# 07_WiFi-BLE.net
KiCad netlist of a schematic drawn in Altium Designer
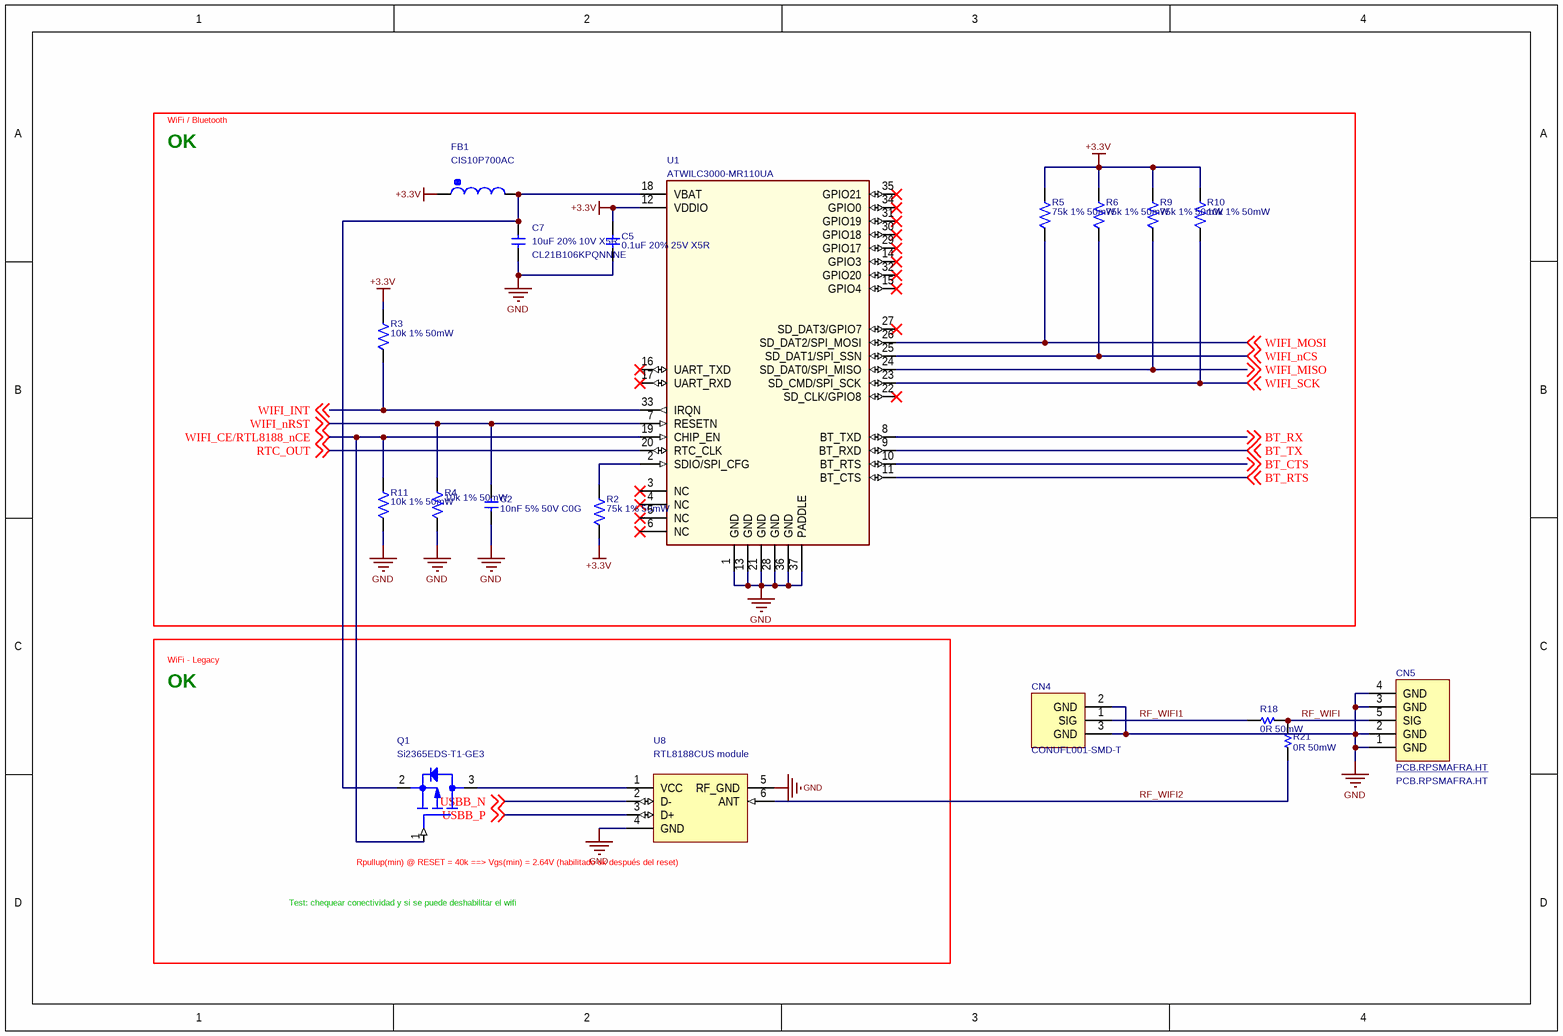
[diagram p0: 07_WiFi-BLE.SchDoc]

(export (version "E")
  (design (tool "Eeschema 10.0.6"))
  (components
    (comp (ref "C2")
      (value "10nF 5% 50V C0G")
      (footprint "CAPC1005N")
      (description "Capacitor, Ceramic")
      (fields
        (field (name "MFG") "<GENERIC>")
        (field (name "TOLERANCE") "5%")
        (field (name "FOOTPRINT CHECKED") "Assign OK, Footprint OK")
      )
      (libsource (lib "components") (part "C"))
    )
    (comp (ref "C5")
      (value "0.1uF 20% 25V X5R")
      (footprint "CAPC1005N")
      (description "Capacitor, Ceramic")
      (fields
        (field (name "MFG") "SAMSUNG")
        (field (name "TOLERANCE") "20%")
        (field (name "FOOTPRINT CHECKED") "Assign OK, Footprint OK")
      )
      (libsource (lib "*") (part "C_Dup1"))
    )
    (comp (ref "C7")
      (value "10uF 20% 10V X5R")
      (footprint "CAPC2012X140N")
      (description "Capacitor, Ceramic")
      (fields
        (field (name "MFG") "SAMSUNG")
        (field (name "MFG_PN") "CL21B106KPQNNNE")
        (field (name "TOLERANCE") "20%")
        (field (name "FOOTPRINT CHECKED") "Assign OK, Footprint OK")
      )
      (libsource (lib "*") (part "C_Dup1"))
    )
    (comp (ref "CN4")
      (value "CONUFL001-SMD-T")
      (footprint "U.FL-R-SMT-1")
      (description "Ultra Small Surface Mount Coaxial Connectors - 1.9mm or 2.4mm Mated Height")
      (fields (field (name "MFG") "LINX") (field (name "FOOTPRINT CHECKED") "Assign OK, Footprint OK"))
      (libsource (lib "traz") (part "U.FL-R-SMT-1"))
    )
    (comp (ref "CN5")
      (value "PCB.RPSMAFRA.HT")
      (footprint "0733910320")
      (description "RP-SMA, Right angle")
      (fields
        (field (name "MFG") "TAOGLAS")
        (field (name "MFG_PN") "PCB.RPSMAFRA.HT")
        (field (name "FOOTPRINT CHECKED") "Assign Ok, Footprint Ok")
      )
      (libsource (lib "xct") (part "RPSMA"))
    )
    (comp (ref "FB1")
      (value "CIS10P700AC")
      (footprint "INDC1608X95N")
      (description "Ferrite Bead")
      (fields (field (name "MFG") "SAMSUNG") (field (name "FOOTPRINT CHECKED") "Assign OK, Footprint OK"))
      (libsource (lib "*") (part "L"))
    )
    (comp (ref "Q1")
      (value "Si2365EDS-T1-GE3")
      (footprint "SOT95P230X110-3N")
      (description "MOSFET, P channel")
      (fields (field (name "MFG") "VISHAY") (field (name "FOOTPRINT CHECKED") "Assign OK, Footprint OK"))
      (libsource (lib "traz") (part "DMG1013UW"))
    )
    (comp (ref "R2")
      (value "75k 1% 50mW")
      (footprint "RESC1005X40N")
      (description "Resistor, SMD")
      (fields
        (field (name "MFG") "<GENERIC>")
        (field (name "POWER") "50mW")
        (field (name "FOOTPRINT CHECKED") "Assign OK, Footprint OK")
      )
      (libsource (lib "*") (part "R"))
    )
    (comp (ref "R3")
      (value "10k 1% 50mW")
      (footprint "RESC1005X40N")
      (description "Resistor, SMD")
      (fields
        (field (name "MFG") "<GENERIC>")
        (field (name "POWER") "50mW")
        (field (name "FOOTPRINT CHECKED") "Assign OK, Footprint OK")
      )
      (libsource (lib "*") (part "R"))
    )
    (comp (ref "R4")
      (value "10k 1% 50mW")
      (footprint "RESC1005X40N")
      (description "Resistor, SMD")
      (fields
        (field (name "MFG") "<GENERIC>")
        (field (name "POWER") "50mW")
        (field (name "FOOTPRINT CHECKED") "Assign OK, Footprint OK")
      )
      (libsource (lib "*") (part "R"))
    )
    (comp (ref "R5")
      (value "75k 1% 50mW")
      (footprint "RESC1005X40N")
      (description "Resistor, SMD")
      (fields
        (field (name "MFG") "<GENERIC>")
        (field (name "POWER") "50mW")
        (field (name "FOOTPRINT CHECKED") "Assign OK, Footprint OK")
      )
      (libsource (lib "*") (part "R"))
    )
    (comp (ref "R6")
      (value "75k 1% 50mW")
      (footprint "RESC1005X40N")
      (description "Resistor, SMD")
      (fields
        (field (name "MFG") "<GENERIC>")
        (field (name "POWER") "50mW")
        (field (name "FOOTPRINT CHECKED") "Assign OK, Footprint OK")
      )
      (libsource (lib "*") (part "R"))
    )
    (comp (ref "R9")
      (value "75k 1% 50mW")
      (footprint "RESC1005X40N")
      (description "Resistor, SMD")
      (fields
        (field (name "MFG") "<GENERIC>")
        (field (name "POWER") "50mW")
        (field (name "FOOTPRINT CHECKED") "Assign OK, Footprint OK")
      )
      (libsource (lib "*") (part "R"))
    )
    (comp (ref "R10")
      (value "10k 1% 50mW")
      (footprint "RESC1005X40N")
      (description "Resistor, SMD")
      (fields
        (field (name "MFG") "<GENERIC>")
        (field (name "POWER") "50mW")
        (field (name "FOOTPRINT CHECKED") "Assign OK, Footprint OK")
      )
      (libsource (lib "*") (part "R"))
    )
    (comp (ref "R11")
      (value "10k 1% 50mW")
      (footprint "RESC1005X40N")
      (description "Resistor, SMD")
      (fields
        (field (name "MFG") "<GENERIC>")
        (field (name "POWER") "50mW")
        (field (name "FOOTPRINT CHECKED") "Assign OK, Footprint OK")
      )
      (libsource (lib "*") (part "R"))
    )
    (comp (ref "R18")
      (value "0R 50mW")
      (footprint "RESC1005X40N")
      (description "Resistor, SMD")
      (fields
        (field (name "MFG") "<GENERIC>")
        (field (name "POWER") "50mW")
        (field (name "FOOTPRINT CHECKED") "Assign OK, Footprint OK")
      )
      (libsource (lib "components") (part "R"))
    )
    (comp (ref "R21")
      (value "0R 50mW")
      (footprint "RESC1005X40N")
      (description "Resistor, SMD")
      (fields
        (field (name "MFG") "<GENERIC>")
        (field (name "POWER") "50mW")
        (field (name "FOOTPRINT CHECKED") "Assign OK, Footprint OK")
      )
      (libsource (lib "components") (part "R"))
    )
    (comp (ref "U1")
      (value "ATWILC3000-MR110UA")
      (footprint "ATWILC3000-MR110CA")
      (description "IEEE 802.11 b/g/n Link Controller Module with Integrated Bluetooth 4.0")
      (fields (field (name "MFG") "MICROCHIP") (field (name "FOOTPRINT CHECKED") "Assign OK, Footprint OK"))
      (libsource (lib "MCHP-CDB") (part "MODULE ATWILC3000-MR110CA"))
    )
    (comp (ref "U8")
      (value "RTL8188CUS module")
      (footprint "GWF-7M01")
      (description "150Mbps IEEE 802.11 b/g/n WiFi Module")
      (fields (field (name "MFG") "FORMIKE") (field (name "FOOTPRINT CHECKED") "Assign OK, Footprint OK"))
      (libsource (lib "traz") (part "GWF-7M01"))
    )
  )
  (nets
    (net (code "1") (name "+3.3V") (class "Default")
      (node (ref "C5") (pin "2") (pinfunction "2_2") (pintype "passive"))
      (node (ref "FB1") (pin "1") (pinfunction "1_1") (pintype "passive"))
      (node (ref "R10") (pin "1") (pinfunction "1_1") (pintype "passive"))
      (node (ref "R2") (pin "2") (pinfunction "2_2") (pintype "passive"))
      (node (ref "R3") (pin "1") (pinfunction "1_1") (pintype "passive"))
      (node (ref "R5") (pin "1") (pinfunction "1_1") (pintype "passive"))
      (node (ref "R6") (pin "1") (pinfunction "1_1") (pintype "passive"))
      (node (ref "R9") (pin "1") (pinfunction "1_1") (pintype "passive"))
      (node (ref "U1") (pin "12") (pinfunction "VDDIO_12") (pintype "power_in"))
    )
    (net (code "2") (name "/RF_WIFI") (class "Default")
      (node (ref "CN5") (pin "5") (pinfunction "SIG_5") (pintype "passive"))
      (node (ref "R18") (pin "2") (pinfunction "2_2") (pintype "passive"))
      (node (ref "R21") (pin "2") (pinfunction "2_2") (pintype "passive"))
    )
    (net (code "3") (name "/RF_WIFI1") (class "Default")
      (node (ref "CN4") (pin "1") (pinfunction "SIG_1") (pintype "passive"))
      (node (ref "R18") (pin "1") (pinfunction "1_1") (pintype "passive"))
    )
    (net (code "4") (name "/RF_WIFI2") (class "Default")
      (node (ref "R21") (pin "1") (pinfunction "1_1") (pintype "passive"))
      (node (ref "U8") (pin "6") (pinfunction "ANT_6") (pintype "input"))
    )
    (net (code "5") (name "BT_CTS") (class "Default")
      (node (ref "U1") (pin "10") (pinfunction "BT_RTS_10") (pintype "bidirectional"))
    )
    (net (code "6") (name "BT_RTS") (class "Default")
      (node (ref "U1") (pin "11") (pinfunction "BT_CTS_11") (pintype "bidirectional"))
    )
    (net (code "7") (name "BT_RX") (class "Default")
      (node (ref "U1") (pin "8") (pinfunction "BT_TXD_8") (pintype "bidirectional"))
    )
    (net (code "8") (name "BT_TX") (class "Default")
      (node (ref "U1") (pin "9") (pinfunction "BT_RXD_9") (pintype "bidirectional"))
    )
    (net (code "9") (name "GND") (class "Default")
      (node (ref "C2") (pin "2") (pinfunction "2_2") (pintype "passive"))
      (node (ref "C5") (pin "1") (pinfunction "1_1") (pintype "passive"))
      (node (ref "C7") (pin "2") (pinfunction "2_2") (pintype "passive"))
      (node (ref "CN4") (pin "2") (pinfunction "GND_2") (pintype "passive"))
      (node (ref "CN4") (pin "3") (pinfunction "GND_3") (pintype "passive"))
      (node (ref "CN5") (pin "1") (pinfunction "GND_1") (pintype "passive"))
      (node (ref "CN5") (pin "2") (pinfunction "GND_2") (pintype "passive"))
      (node (ref "CN5") (pin "3") (pinfunction "GND_3") (pintype "passive"))
      (node (ref "CN5") (pin "4") (pinfunction "GND_4") (pintype "passive"))
      (node (ref "R11") (pin "2") (pinfunction "2_2") (pintype "passive"))
      (node (ref "R4") (pin "2") (pinfunction "2_2") (pintype "passive"))
      (node (ref "U1") (pin "1") (pinfunction "GND_1") (pintype "power_in"))
      (node (ref "U1") (pin "13") (pinfunction "GND_13") (pintype "power_in"))
      (node (ref "U1") (pin "21") (pinfunction "GND_21") (pintype "power_in"))
      (node (ref "U1") (pin "28") (pinfunction "GND_28") (pintype "power_in"))
      (node (ref "U1") (pin "36") (pinfunction "GND_36") (pintype "power_in"))
      (node (ref "U1") (pin "37") (pinfunction "PADDLE_37") (pintype "power_in"))
      (node (ref "U8") (pin "4") (pinfunction "GND_4") (pintype "power_in"))
      (node (ref "U8") (pin "5") (pinfunction "RF_GND_5") (pintype "power_in"))
    )
    (net (code "10") (name "Net-(Q1-DRAIN)") (class "Default")
      (node (ref "Q1") (pin "3") (pinfunction "DRAIN_3") (pintype "passive"))
      (node (ref "U8") (pin "1") (pinfunction "VCC_1") (pintype "power_in"))
    )
    (net (code "11") (name "Net-(Q1-SOURCE)") (class "Default")
      (node (ref "C7") (pin "1") (pinfunction "1_1") (pintype "passive"))
      (node (ref "FB1") (pin "2") (pinfunction "2_2") (pintype "passive"))
      (node (ref "Q1") (pin "2") (pinfunction "SOURCE_2") (pintype "passive"))
      (node (ref "U1") (pin "18") (pinfunction "VBAT_18") (pintype "power_in"))
    )
    (net (code "12") (name "Net-(U1-SDIO{slash}SPI_CFG)") (class "Default")
      (node (ref "R2") (pin "1") (pinfunction "1_1") (pintype "passive"))
      (node (ref "U1") (pin "2") (pinfunction "SDIO/SPI_CFG_2") (pintype "input"))
    )
    (net (code "13") (name "RTC_OUT") (class "Default")
      (node (ref "U1") (pin "20") (pinfunction "RTC_CLK_20") (pintype "bidirectional"))
    )
    (net (code "14") (name "USBB_N") (class "Default")
      (node (ref "U8") (pin "2") (pinfunction "D-_2") (pintype "bidirectional"))
    )
    (net (code "15") (name "USBB_P") (class "Default")
      (node (ref "U8") (pin "3") (pinfunction "D+_3") (pintype "bidirectional"))
    )
    (net (code "16") (name "WIFI_CE{slash}RTL8188_nCE") (class "Default")
      (node (ref "Q1") (pin "1") (pinfunction "GATE_1") (pintype "input"))
      (node (ref "R11") (pin "1") (pinfunction "1_1") (pintype "passive"))
      (node (ref "U1") (pin "19") (pinfunction "CHIP_EN_19") (pintype "input"))
    )
    (net (code "17") (name "WIFI_INT") (class "Default")
      (node (ref "R3") (pin "2") (pinfunction "2_2") (pintype "passive"))
      (node (ref "U1") (pin "33") (pinfunction "IRQN_33") (pintype "output"))
    )
    (net (code "18") (name "WIFI_MISO") (class "Default")
      (node (ref "R9") (pin "2") (pinfunction "2_2") (pintype "passive"))
      (node (ref "U1") (pin "24") (pinfunction "SD_DAT0/SPI_MISO_24") (pintype "bidirectional"))
    )
    (net (code "19") (name "WIFI_MOSI") (class "Default")
      (node (ref "R5") (pin "2") (pinfunction "2_2") (pintype "passive"))
      (node (ref "U1") (pin "26") (pinfunction "SD_DAT2/SPI_MOSI_26") (pintype "bidirectional"))
    )
    (net (code "20") (name "WIFI_SCK") (class "Default")
      (node (ref "R10") (pin "2") (pinfunction "2_2") (pintype "passive"))
      (node (ref "U1") (pin "23") (pinfunction "SD_CMD/SPI_SCK_23") (pintype "bidirectional"))
    )
    (net (code "21") (name "WIFI_nCS") (class "Default")
      (node (ref "R6") (pin "2") (pinfunction "2_2") (pintype "passive"))
      (node (ref "U1") (pin "25") (pinfunction "SD_DAT1/SPI_SSN_25") (pintype "bidirectional"))
    )
    (net (code "22") (name "WIFI_nRST") (class "Default")
      (node (ref "C2") (pin "1") (pinfunction "1_1") (pintype "passive"))
      (node (ref "R4") (pin "1") (pinfunction "1_1") (pintype "passive"))
      (node (ref "U1") (pin "7") (pinfunction "RESETN_7") (pintype "input"))
    )
    (net (code "23") (name "unconnected-(U1-GPIO0-Pad34)") (class "Default")
      (node (ref "U1") (pin "34") (pinfunction "GPIO0_34") (pintype "bidirectional+no_connect"))
    )
    (net (code "24") (name "unconnected-(U1-GPIO3-Pad14)") (class "Default")
      (node (ref "U1") (pin "14") (pinfunction "GPIO3_14") (pintype "bidirectional+no_connect"))
    )
    (net (code "25") (name "unconnected-(U1-GPIO4-Pad15)") (class "Default")
      (node (ref "U1") (pin "15") (pinfunction "GPIO4_15") (pintype "bidirectional+no_connect"))
    )
    (net (code "26") (name "unconnected-(U1-GPIO17-Pad29)") (class "Default")
      (node (ref "U1") (pin "29") (pinfunction "GPIO17_29") (pintype "bidirectional+no_connect"))
    )
    (net (code "27") (name "unconnected-(U1-GPIO18-Pad30)") (class "Default")
      (node (ref "U1") (pin "30") (pinfunction "GPIO18_30") (pintype "bidirectional+no_connect"))
    )
    (net (code "28") (name "unconnected-(U1-GPIO19-Pad31)") (class "Default")
      (node (ref "U1") (pin "31") (pinfunction "GPIO19_31") (pintype "bidirectional+no_connect"))
    )
    (net (code "29") (name "unconnected-(U1-GPIO20-Pad32)") (class "Default")
      (node (ref "U1") (pin "32") (pinfunction "GPIO20_32") (pintype "bidirectional+no_connect"))
    )
    (net (code "30") (name "unconnected-(U1-GPIO21-Pad35)") (class "Default")
      (node (ref "U1") (pin "35") (pinfunction "GPIO21_35") (pintype "bidirectional+no_connect"))
    )
    (net (code "31") (name "unconnected-(U1-NC-Pad3)") (class "Default")
      (node (ref "U1") (pin "3") (pinfunction "NC_3") (pintype "passive+no_connect"))
    )
    (net (code "32") (name "unconnected-(U1-NC-Pad4)") (class "Default")
      (node (ref "U1") (pin "4") (pinfunction "NC_4") (pintype "passive+no_connect"))
    )
    (net (code "33") (name "unconnected-(U1-NC-Pad5)") (class "Default")
      (node (ref "U1") (pin "5") (pinfunction "NC_5") (pintype "passive+no_connect"))
    )
    (net (code "34") (name "unconnected-(U1-NC-Pad6)") (class "Default")
      (node (ref "U1") (pin "6") (pinfunction "NC_6") (pintype "passive+no_connect"))
    )
    (net (code "35") (name "unconnected-(U1-SD_CLK{slash}GPIO8-Pad22)") (class "Default")
      (node (ref "U1") (pin "22") (pinfunction "SD_CLK/GPIO8_22") (pintype "bidirectional+no_connect"))
    )
    (net (code "36") (name "unconnected-(U1-SD_DAT3{slash}GPIO7-Pad27)") (class "Default")
      (node (ref "U1") (pin "27") (pinfunction "SD_DAT3/GPIO7_27") (pintype "bidirectional+no_connect"))
    )
    (net (code "37") (name "unconnected-(U1-UART_RXD-Pad17)") (class "Default")
      (node (ref "U1") (pin "17") (pinfunction "UART_RXD_17") (pintype "bidirectional+no_connect"))
    )
    (net (code "38") (name "unconnected-(U1-UART_TXD-Pad16)") (class "Default")
      (node (ref "U1") (pin "16") (pinfunction "UART_TXD_16") (pintype "bidirectional+no_connect"))
    )
  )
)
